# Buck-Boost_converter.net
KiCad netlist of a schematic drawn in Altium Designer
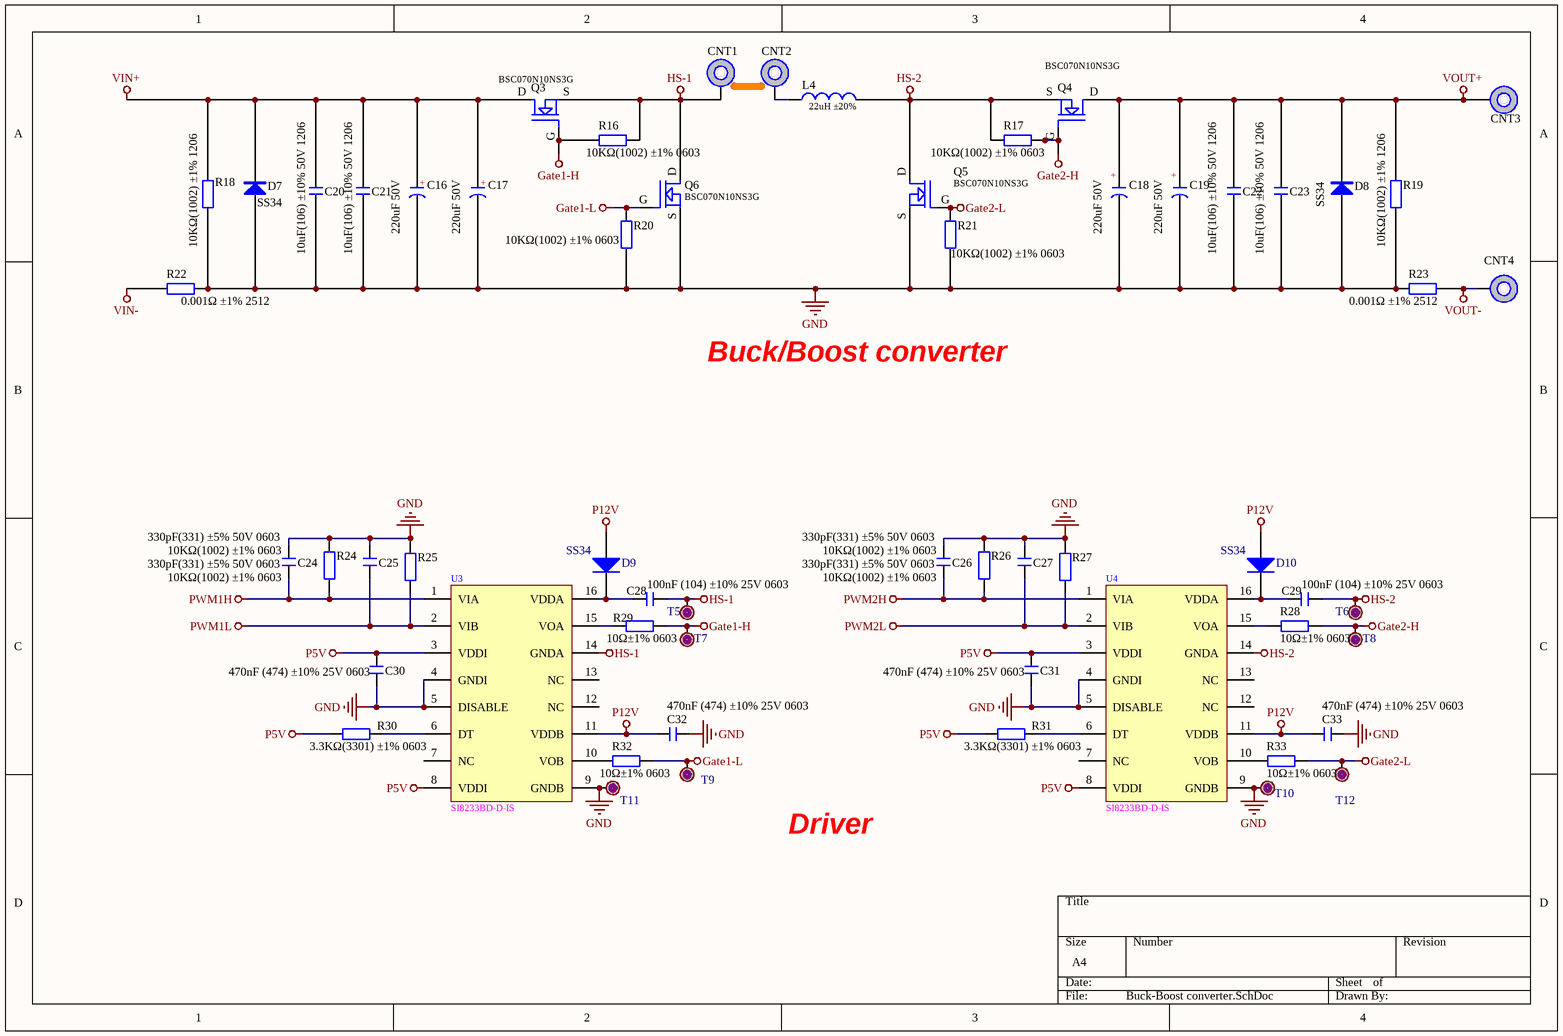
[diagram p0: Buck-Boost converter.SchDoc]

(export (version "E")
  (design (tool "Eeschema 10.0.6"))
  (components
    (comp (ref "C16")
      (value "220uF 50V")
      (footprint "CE F(10*10.2)")
      (description "直插电解电容")
      (libsource (lib "") (part "CE_1"))
    )
    (comp (ref "C17")
      (value "220uF 50V")
      (footprint "1.10-电容:CE F(10*10.2)")
      (description "直插电解电容")
      (libsource (lib "") (part "CE_1"))
    )
    (comp (ref "C18")
      (value "220uF 50V")
      (footprint "CE F(10*10.2)")
      (description "直插电解电容")
      (libsource (lib "0.1 - 电阻-电容-电感") (part "CE"))
    )
    (comp (ref "C19")
      (value "220uF 50V")
      (footprint "CE F(10*10.2)")
      (description "直插电解电容")
      (libsource (lib "0.1 - 电阻-电容-电感") (part "CE"))
    )
    (comp (ref "C20")
      (value "10uF(106) ±10% 50V 1206")
      (footprint "C 1206_M")
      (description "贴片电容")
      (libsource (lib "0.1 - 电阻-电容-电感") (part "C"))
    )
    (comp (ref "C21")
      (value "10uF(106) ±10% 50V 1206")
      (footprint "C 1206_M")
      (description "贴片电容")
      (libsource (lib "0.1 - 电阻-电容-电感") (part "C"))
    )
    (comp (ref "C22")
      (value "10uF(106) ±10% 50V 1206")
      (footprint "C 1206_M")
      (description "贴片电容")
      (libsource (lib "0.1 - 电阻-电容-电感") (part "C"))
    )
    (comp (ref "C23")
      (value "10uF(106) ±10% 50V 1206")
      (footprint "C 1206_M")
      (description "贴片电容")
      (libsource (lib "0.1 - 电阻-电容-电感") (part "C"))
    )
    (comp (ref "C24")
      (value "330pF(331) ±5% 50V 0603")
      (footprint "C 0603_L")
      (description "贴片电容")
      (libsource (lib "0.1 - 电阻-电容-电感") (part "C"))
    )
    (comp (ref "C25")
      (value "330pF(331) ±5% 50V 0603")
      (footprint "C 0603_L")
      (description "贴片电容")
      (libsource (lib "0.1 - 电阻-电容-电感") (part "C"))
    )
    (comp (ref "C26")
      (value "330pF(331) ±5% 50V 0603")
      (footprint "C 0603_L")
      (description "贴片电容")
      (libsource (lib "0.1 - 电阻-电容-电感") (part "C"))
    )
    (comp (ref "C27")
      (value "330pF(331) ±5% 50V 0603")
      (footprint "C 0603_L")
      (description "贴片电容")
      (libsource (lib "0.1 - 电阻-电容-电感") (part "C"))
    )
    (comp (ref "C28")
      (value "100nF (104) ±10% 25V 0603")
      (footprint "C 0603_L")
      (description "贴片电容")
      (libsource (lib "0.1 - 电阻-电容-电感") (part "C"))
    )
    (comp (ref "C29")
      (value "100nF (104) ±10% 25V 0603")
      (footprint "C 0603_L")
      (description "贴片电容")
      (libsource (lib "0.1 - 电阻-电容-电感") (part "C"))
    )
    (comp (ref "C30")
      (value "470nF (474) ±10% 25V 0603")
      (footprint "C 0603_L")
      (description "贴片电容")
      (libsource (lib "0.1 - 电阻-电容-电感") (part "C"))
    )
    (comp (ref "C31")
      (value "470nF (474) ±10% 25V 0603")
      (footprint "C 0603_L")
      (description "贴片电容")
      (libsource (lib "0.1 - 电阻-电容-电感") (part "C"))
    )
    (comp (ref "C32")
      (value "470nF (474) ±10% 25V 0603")
      (footprint "C 0603_L")
      (description "贴片电容")
      (libsource (lib "0.1 - 电阻-电容-电感") (part "C"))
    )
    (comp (ref "C33")
      (value "470nF (474) ±10% 25V 0603")
      (footprint "C 0603_L")
      (description "贴片电容")
      (libsource (lib "0.1 - 电阻-电容-电感") (part "C"))
    )
    (comp (ref "CNT1") (value "CST") (footprint "M3") (libsource (lib "Schlib2") (part "SO3040")))
    (comp (ref "CNT2") (value "CST") (footprint "M3") (libsource (lib "Schlib2") (part "SO3040")))
    (comp (ref "CNT3") (value "CST") (footprint "M3") (libsource (lib "Schlib2") (part "SO3040")))
    (comp (ref "CNT4") (value "CST") (footprint "M3") (libsource (lib "Schlib2") (part "SO3040")))
    (comp (ref "D7")
      (value "SS34")
      (footprint "SMA")
      (description "整流二极管")
      (libsource (lib "0.2 - 二极管-整流桥") (part "1N4007"))
    )
    (comp (ref "D8")
      (value "SS34")
      (footprint "SMA")
      (description "整流二极管")
      (libsource (lib "0.2 - 二极管-整流桥") (part "1N4007"))
    )
    (comp (ref "D9")
      (value "SS34")
      (footprint "SMA")
      (description "Default Diode")
      (libsource (lib "Miscellaneous Devices") (part "Diode"))
    )
    (comp (ref "D10")
      (value "SS34")
      (footprint "SMA")
      (description "Default Diode")
      (libsource (lib "Miscellaneous Devices") (part "Diode"))
    )
    (comp (ref "L4")
      (value "22uH ±20%")
      (footprint "L-SMD-0630")
      (description "Inductor")
      (libsource (lib "034110_D2DPOWER_V2") (part "Inductor"))
    )
    (comp (ref "Q3")
      (value "BSC070N10NS3G")
      (footprint "PG-TDSON-8_5x6MM")
      (libsource (lib "*") (part "MOSFET N"))
    )
    (comp (ref "Q4")
      (value "BSC070N10NS3G")
      (footprint "PG-TDSON-8_5x6MM")
      (libsource (lib "*") (part "MOSFET N"))
    )
    (comp (ref "Q5")
      (value "BSC070N10NS3G")
      (footprint "PG-TDSON-8_5x6MM")
      (libsource (lib "*") (part "MOSFET N"))
    )
    (comp (ref "Q6")
      (value "BSC070N10NS3G")
      (footprint "PG-TDSON-8_5x6MM")
      (libsource (lib "*") (part "MOSFET N"))
    )
    (comp (ref "R16")
      (value "10KΩ(1002) ±1% 0603")
      (footprint "R 0603_L")
      (description "贴片电阻")
      (fields (field (name "版权归属") "来自淘宝 ID：黄晶宝石"))
      (libsource (lib "0.1 - 电阻-电容-电感") (part "R"))
    )
    (comp (ref "R17")
      (value "10KΩ(1002) ±1% 0603")
      (footprint "R 0603_L")
      (description "贴片电阻")
      (fields (field (name "版权归属") "来自淘宝 ID：黄晶宝石"))
      (libsource (lib "0.1 - 电阻-电容-电感") (part "R"))
    )
    (comp (ref "R18")
      (value "10KΩ(1002) ±1% 1206")
      (footprint "R 1206_L")
      (description "贴片电阻")
      (fields (field (name "版权归属") "来自淘宝 ID：黄晶宝石"))
      (libsource (lib "0.1 - 电阻-电容-电感") (part "R"))
    )
    (comp (ref "R19")
      (value "10KΩ(1002) ±1% 1206")
      (footprint "R 1206_L")
      (description "贴片电阻")
      (fields (field (name "版权归属") "来自淘宝 ID：黄晶宝石"))
      (libsource (lib "0.1 - 电阻-电容-电感") (part "R"))
    )
    (comp (ref "R20")
      (value "10KΩ(1002) ±1% 0603")
      (footprint "R 0603_L")
      (description "贴片电阻")
      (fields (field (name "版权归属") "来自淘宝 ID：黄晶宝石"))
      (libsource (lib "0.1 - 电阻-电容-电感") (part "R"))
    )
    (comp (ref "R21")
      (value "10KΩ(1002) ±1% 0603")
      (footprint "R 0603_L")
      (description "贴片电阻")
      (fields (field (name "版权归属") "来自淘宝 ID：黄晶宝石"))
      (libsource (lib "0.1 - 电阻-电容-电感") (part "R"))
    )
    (comp (ref "R22")
      (value "0.001Ω ±1% 2512")
      (footprint "R2512")
      (description "贴片电阻")
      (fields (field (name "版权归属") "来自淘宝 ID：黄晶宝石"))
      (libsource (lib "0.1 - 电阻-电容-电感") (part "R"))
    )
    (comp (ref "R23")
      (value "0.001Ω ±1% 2512")
      (footprint "R2512")
      (description "贴片电阻")
      (fields (field (name "版权归属") "来自淘宝 ID：黄晶宝石"))
      (libsource (lib "0.1 - 电阻-电容-电感") (part "R"))
    )
    (comp (ref "R24")
      (value "10KΩ(1002) ±1% 0603")
      (footprint "R 0603_L")
      (description "贴片电阻")
      (fields (field (name "版权归属") "来自淘宝 ID：黄晶宝石"))
      (libsource (lib "0.1 - 电阻-电容-电感") (part "R"))
    )
    (comp (ref "R25")
      (value "10KΩ(1002) ±1% 0603")
      (footprint "R 0603_L")
      (description "贴片电阻")
      (fields (field (name "版权归属") "来自淘宝 ID：黄晶宝石"))
      (libsource (lib "0.1 - 电阻-电容-电感") (part "R"))
    )
    (comp (ref "R26")
      (value "10KΩ(1002) ±1% 0603")
      (footprint "R0805_L")
      (description "贴片电阻")
      (fields (field (name "版权归属") "来自淘宝 ID：黄晶宝石"))
      (libsource (lib "0.1 - 电阻-电容-电感") (part "R"))
    )
    (comp (ref "R27")
      (value "10KΩ(1002) ±1% 0603")
      (footprint "R 0603_L")
      (description "贴片电阻")
      (fields (field (name "版权归属") "来自淘宝 ID：黄晶宝石"))
      (libsource (lib "0.1 - 电阻-电容-电感") (part "R"))
    )
    (comp (ref "R28")
      (value "10Ω±1% 0603")
      (footprint "R 0603_L")
      (description "贴片电阻")
      (fields (field (name "版权归属") "来自淘宝 ID：黄晶宝石"))
      (libsource (lib "0.1 - 电阻-电容-电感") (part "R"))
    )
    (comp (ref "R29")
      (value "10Ω±1% 0603")
      (footprint "R 0603_L")
      (description "贴片电阻")
      (fields (field (name "版权归属") "来自淘宝 ID：黄晶宝石"))
      (libsource (lib "0.1 - 电阻-电容-电感") (part "R"))
    )
    (comp (ref "R30")
      (value "3.3KΩ(3301) ±1% 0603")
      (footprint "R 0603_L")
      (description "贴片电阻")
      (fields (field (name "版权归属") "来自淘宝 ID：黄晶宝石"))
      (libsource (lib "0.1 - 电阻-电容-电感") (part "R"))
    )
    (comp (ref "R31")
      (value "3.3KΩ(3301) ±1% 0603")
      (footprint "R 0603_L")
      (description "贴片电阻")
      (fields (field (name "版权归属") "来自淘宝 ID：黄晶宝石"))
      (libsource (lib "0.1 - 电阻-电容-电感") (part "R"))
    )
    (comp (ref "R32")
      (value "10Ω±1% 0603")
      (footprint "R 0603_L")
      (description "贴片电阻")
      (fields (field (name "版权归属") "来自淘宝 ID：黄晶宝石"))
      (libsource (lib "0.1 - 电阻-电容-电感") (part "R"))
    )
    (comp (ref "R33")
      (value "10Ω±1% 0603")
      (footprint "R 0603_L")
      (description "贴片电阻")
      (fields (field (name "版权归属") "来自淘宝 ID：黄晶宝石"))
      (libsource (lib "0.1 - 电阻-电容-电感") (part "R"))
    )
    (comp (ref "T5") (value "TestP") (footprint "TestP") (libsource (lib "CSS02404A") (part "TestP")))
    (comp (ref "T6") (value "TestP") (footprint "TestP") (libsource (lib "CSS02404A") (part "TestP")))
    (comp (ref "T7") (value "TestP") (footprint "TestP") (libsource (lib "CSS02404A") (part "TestP")))
    (comp (ref "T8") (value "TestP") (footprint "TestP") (libsource (lib "CSS02404A") (part "TestP")))
    (comp (ref "T9") (value "TestP") (footprint "TestP") (libsource (lib "CSS02404A") (part "TestP")))
    (comp (ref "T10") (value "TestP") (footprint "TestP") (libsource (lib "CSS02404A") (part "TestP")))
    (comp (ref "T11") (value "TestP") (footprint "TestP") (libsource (lib "CSS02404A") (part "TestP")))
    (comp (ref "T12") (value "TestP") (footprint "TestP") (libsource (lib "CSS02404A") (part "TestP")))
    (comp (ref "U3") (value "SI8233BD-D-IS") (footprint "SOJ16T") (libsource (lib "Si8234") (part "Si8233")))
    (comp (ref "U4") (value "SI8233BD-D-IS") (footprint "SOJ16T") (libsource (lib "Si8234") (part "Si8233")))
  )
  (nets
    (net (code "1") (name "GND") (class "Default")
      (node (ref "C16") (pin "2") (pinfunction "K_2") (pintype "passive"))
      (node (ref "C17") (pin "2") (pinfunction "K_2") (pintype "passive"))
      (node (ref "C18") (pin "2") (pinfunction "K_2") (pintype "passive"))
      (node (ref "C19") (pin "2") (pinfunction "K_2") (pintype "passive"))
      (node (ref "C20") (pin "1") (pinfunction "1_1") (pintype "passive"))
      (node (ref "C21") (pin "1") (pinfunction "1_1") (pintype "passive"))
      (node (ref "C22") (pin "1") (pinfunction "1_1") (pintype "passive"))
      (node (ref "C23") (pin "1") (pinfunction "1_1") (pintype "passive"))
      (node (ref "C24") (pin "2") (pinfunction "2_2") (pintype "passive"))
      (node (ref "C25") (pin "2") (pinfunction "2_2") (pintype "passive"))
      (node (ref "C26") (pin "2") (pinfunction "2_2") (pintype "passive"))
      (node (ref "C27") (pin "2") (pinfunction "2_2") (pintype "passive"))
      (node (ref "C30") (pin "2") (pinfunction "2_2") (pintype "passive"))
      (node (ref "C31") (pin "2") (pinfunction "2_2") (pintype "passive"))
      (node (ref "C32") (pin "1") (pinfunction "1_1") (pintype "passive"))
      (node (ref "C33") (pin "1") (pinfunction "1_1") (pintype "passive"))
      (node (ref "D7") (pin "1") (pinfunction "A_1") (pintype "passive"))
      (node (ref "D8") (pin "1") (pinfunction "A_1") (pintype "passive"))
      (node (ref "Q5") (pin "S") (pinfunction "SOURCE_S") (pintype "passive"))
      (node (ref "Q6") (pin "S") (pinfunction "SOURCE_S") (pintype "passive"))
      (node (ref "R18") (pin "1") (pinfunction "1_1") (pintype "passive"))
      (node (ref "R19") (pin "1") (pinfunction "1_1") (pintype "passive"))
      (node (ref "R20") (pin "1") (pinfunction "1_1") (pintype "passive"))
      (node (ref "R21") (pin "1") (pinfunction "1_1") (pintype "passive"))
      (node (ref "R22") (pin "1") (pinfunction "1_1") (pintype "passive"))
      (node (ref "R23") (pin "1") (pinfunction "1_1") (pintype "passive"))
      (node (ref "R24") (pin "2") (pinfunction "2_2") (pintype "passive"))
      (node (ref "R25") (pin "2") (pinfunction "2_2") (pintype "passive"))
      (node (ref "R26") (pin "2") (pinfunction "2_2") (pintype "passive"))
      (node (ref "R27") (pin "2") (pinfunction "2_2") (pintype "passive"))
      (node (ref "T10") (pin "0") (pinfunction "0_0") (pintype "passive"))
      (node (ref "T11") (pin "0") (pinfunction "0_0") (pintype "passive"))
      (node (ref "U3") (pin "4") (pinfunction "GNDI_4") (pintype "passive"))
      (node (ref "U3") (pin "5") (pinfunction "DISABLE_5") (pintype "passive"))
      (node (ref "U3") (pin "9") (pinfunction "GNDB_9") (pintype "passive"))
      (node (ref "U4") (pin "4") (pinfunction "GNDI_4") (pintype "passive"))
      (node (ref "U4") (pin "5") (pinfunction "DISABLE_5") (pintype "passive"))
      (node (ref "U4") (pin "9") (pinfunction "GNDB_9") (pintype "passive"))
    )
    (net (code "2") (name "Gate1-H") (class "Default")
      (node (ref "Q3") (pin "G") (pinfunction "GATE_G") (pintype "passive"))
      (node (ref "R16") (pin "1") (pinfunction "1_1") (pintype "passive"))
      (node (ref "R29") (pin "1") (pinfunction "1_1") (pintype "passive"))
      (node (ref "T7") (pin "0") (pinfunction "0_0") (pintype "passive"))
    )
    (net (code "3") (name "Gate1-L") (class "Default")
      (node (ref "Q6") (pin "G") (pinfunction "GATE_G") (pintype "passive"))
      (node (ref "R20") (pin "2") (pinfunction "2_2") (pintype "passive"))
      (node (ref "R32") (pin "1") (pinfunction "1_1") (pintype "passive"))
      (node (ref "T9") (pin "0") (pinfunction "0_0") (pintype "passive"))
    )
    (net (code "4") (name "Gate2-H") (class "Default")
      (node (ref "Q4") (pin "G") (pinfunction "GATE_G") (pintype "passive"))
      (node (ref "R17") (pin "1") (pinfunction "1_1") (pintype "passive"))
      (node (ref "R28") (pin "1") (pinfunction "1_1") (pintype "passive"))
      (node (ref "T8") (pin "0") (pinfunction "0_0") (pintype "passive"))
    )
    (net (code "5") (name "Gate2-L") (class "Default")
      (node (ref "Q5") (pin "G") (pinfunction "GATE_G") (pintype "passive"))
      (node (ref "R21") (pin "2") (pinfunction "2_2") (pintype "passive"))
      (node (ref "R33") (pin "1") (pinfunction "1_1") (pintype "passive"))
      (node (ref "T12") (pin "0") (pinfunction "0_0") (pintype "passive"))
    )
    (net (code "6") (name "HS-1") (class "Default")
      (node (ref "C28") (pin "2") (pinfunction "2_2") (pintype "passive"))
      (node (ref "CNT1") (pin "1") (pinfunction "1_1") (pintype "passive"))
      (node (ref "Q3") (pin "S") (pinfunction "SOURCE_S") (pintype "passive"))
      (node (ref "Q6") (pin "D") (pinfunction "DRAIN_D") (pintype "passive"))
      (node (ref "R16") (pin "2") (pinfunction "2_2") (pintype "passive"))
      (node (ref "T5") (pin "0") (pinfunction "0_0") (pintype "passive"))
      (node (ref "U3") (pin "14") (pinfunction "GNDA_14") (pintype "passive"))
    )
    (net (code "7") (name "HS-2") (class "Default")
      (node (ref "C29") (pin "2") (pinfunction "2_2") (pintype "passive"))
      (node (ref "L4") (pin "2") (pintype "passive"))
      (node (ref "Q4") (pin "S") (pinfunction "SOURCE_S") (pintype "passive"))
      (node (ref "Q5") (pin "D") (pinfunction "DRAIN_D") (pintype "passive"))
      (node (ref "R17") (pin "2") (pinfunction "2_2") (pintype "passive"))
      (node (ref "T6") (pin "0") (pinfunction "0_0") (pintype "passive"))
      (node (ref "U4") (pin "14") (pinfunction "GNDA_14") (pintype "passive"))
    )
    (net (code "8") (name "Net-(CNT2-Pad1)_1") (class "Default")
      (node (ref "CNT2") (pin "1") (pinfunction "1_1") (pintype "passive"))
      (node (ref "L4") (pin "1") (pintype "passive"))
    )
    (net (code "9") (name "Net-(D9-K)") (class "Default")
      (node (ref "C28") (pin "1") (pinfunction "1_1") (pintype "passive"))
      (node (ref "D9") (pin "2") (pinfunction "K_2") (pintype "passive"))
      (node (ref "U3") (pin "16") (pinfunction "VDDA_16") (pintype "passive"))
    )
    (net (code "10") (name "Net-(D10-K)") (class "Default")
      (node (ref "C29") (pin "1") (pinfunction "1_1") (pintype "passive"))
      (node (ref "D10") (pin "2") (pinfunction "K_2") (pintype "passive"))
      (node (ref "U4") (pin "16") (pinfunction "VDDA_16") (pintype "passive"))
    )
    (net (code "11") (name "Net-(U3-DT)") (class "Default")
      (node (ref "R30") (pin "1") (pinfunction "1_1") (pintype "passive"))
      (node (ref "U3") (pin "6") (pinfunction "DT_6") (pintype "passive"))
    )
    (net (code "12") (name "Net-(U3-VOA)") (class "Default")
      (node (ref "R29") (pin "2") (pinfunction "2_2") (pintype "passive"))
      (node (ref "U3") (pin "15") (pinfunction "VOA_15") (pintype "passive"))
    )
    (net (code "13") (name "Net-(U3-VOB)") (class "Default")
      (node (ref "R32") (pin "2") (pinfunction "2_2") (pintype "passive"))
      (node (ref "U3") (pin "10") (pinfunction "VOB_10") (pintype "passive"))
    )
    (net (code "14") (name "Net-(U4-DT)") (class "Default")
      (node (ref "R31") (pin "1") (pinfunction "1_1") (pintype "passive"))
      (node (ref "U4") (pin "6") (pinfunction "DT_6") (pintype "passive"))
    )
    (net (code "15") (name "Net-(U4-VOA)") (class "Default")
      (node (ref "R28") (pin "2") (pinfunction "2_2") (pintype "passive"))
      (node (ref "U4") (pin "15") (pinfunction "VOA_15") (pintype "passive"))
    )
    (net (code "16") (name "Net-(U4-VOB)") (class "Default")
      (node (ref "R33") (pin "2") (pinfunction "2_2") (pintype "passive"))
      (node (ref "U4") (pin "10") (pinfunction "VOB_10") (pintype "passive"))
    )
    (net (code "17") (name "P5V") (class "Default")
      (node (ref "C30") (pin "1") (pinfunction "1_1") (pintype "passive"))
      (node (ref "C31") (pin "1") (pinfunction "1_1") (pintype "passive"))
      (node (ref "R30") (pin "2") (pinfunction "2_2") (pintype "passive"))
      (node (ref "R31") (pin "2") (pinfunction "2_2") (pintype "passive"))
      (node (ref "U3") (pin "3") (pinfunction "VDDI_3") (pintype "passive"))
      (node (ref "U3") (pin "8") (pinfunction "VDDI_8") (pintype "passive"))
      (node (ref "U4") (pin "3") (pinfunction "VDDI_3") (pintype "passive"))
      (node (ref "U4") (pin "8") (pinfunction "VDDI_8") (pintype "passive"))
    )
    (net (code "18") (name "P12V") (class "Default")
      (node (ref "C32") (pin "2") (pinfunction "2_2") (pintype "passive"))
      (node (ref "C33") (pin "2") (pinfunction "2_2") (pintype "passive"))
      (node (ref "D10") (pin "1") (pinfunction "A_1") (pintype "passive"))
      (node (ref "D9") (pin "1") (pinfunction "A_1") (pintype "passive"))
      (node (ref "U3") (pin "11") (pinfunction "VDDB_11") (pintype "passive"))
      (node (ref "U4") (pin "11") (pinfunction "VDDB_11") (pintype "passive"))
    )
    (net (code "19") (name "PWM1H") (class "Default")
      (node (ref "C24") (pin "1") (pinfunction "1_1") (pintype "passive"))
      (node (ref "R24") (pin "1") (pinfunction "1_1") (pintype "passive"))
      (node (ref "U3") (pin "1") (pinfunction "VIA_1") (pintype "passive"))
    )
    (net (code "20") (name "PWM1L") (class "Default")
      (node (ref "C25") (pin "1") (pinfunction "1_1") (pintype "passive"))
      (node (ref "R25") (pin "1") (pinfunction "1_1") (pintype "passive"))
      (node (ref "U3") (pin "2") (pinfunction "VIB_2") (pintype "passive"))
    )
    (net (code "21") (name "PWM2H") (class "Default")
      (node (ref "C26") (pin "1") (pinfunction "1_1") (pintype "passive"))
      (node (ref "R26") (pin "1") (pinfunction "1_1") (pintype "passive"))
      (node (ref "U4") (pin "1") (pinfunction "VIA_1") (pintype "passive"))
    )
    (net (code "22") (name "PWM2L") (class "Default")
      (node (ref "C27") (pin "1") (pinfunction "1_1") (pintype "passive"))
      (node (ref "R27") (pin "1") (pinfunction "1_1") (pintype "passive"))
      (node (ref "U4") (pin "2") (pinfunction "VIB_2") (pintype "passive"))
    )
    (net (code "23") (name "VIN+") (class "Default")
      (node (ref "C16") (pin "1") (pinfunction "A_1") (pintype "passive"))
      (node (ref "C17") (pin "1") (pinfunction "A_1") (pintype "passive"))
      (node (ref "C20") (pin "2") (pinfunction "2_2") (pintype "passive"))
      (node (ref "C21") (pin "2") (pinfunction "2_2") (pintype "passive"))
      (node (ref "D7") (pin "2") (pinfunction "K_2") (pintype "passive"))
      (node (ref "Q3") (pin "D") (pinfunction "DRAIN_D") (pintype "passive"))
      (node (ref "R18") (pin "2") (pinfunction "2_2") (pintype "passive"))
    )
    (net (code "24") (name "VIN-") (class "Default")
      (node (ref "R22") (pin "2") (pinfunction "2_2") (pintype "passive"))
    )
    (net (code "25") (name "VOUT+") (class "Default")
      (node (ref "C18") (pin "1") (pinfunction "A_1") (pintype "passive"))
      (node (ref "C19") (pin "1") (pinfunction "A_1") (pintype "passive"))
      (node (ref "C22") (pin "2") (pinfunction "2_2") (pintype "passive"))
      (node (ref "C23") (pin "2") (pinfunction "2_2") (pintype "passive"))
      (node (ref "CNT3") (pin "1") (pinfunction "1_1") (pintype "passive"))
      (node (ref "D8") (pin "2") (pinfunction "K_2") (pintype "passive"))
      (node (ref "Q4") (pin "D") (pinfunction "DRAIN_D") (pintype "passive"))
      (node (ref "R19") (pin "2") (pinfunction "2_2") (pintype "passive"))
    )
    (net (code "26") (name "VOUT-") (class "Default")
      (node (ref "CNT4") (pin "1") (pinfunction "1_1") (pintype "passive"))
      (node (ref "R23") (pin "2") (pinfunction "2_2") (pintype "passive"))
    )
    (net (code "27") (name "unconnected-(CNT1-Pad1)") (class "Default")
      (node (ref "CNT1") (pin "1") (pinfunction "1_1") (pintype "passive"))
    )
    (net (code "28") (name "unconnected-(CNT1-Pad1)_1") (class "Default")
      (node (ref "CNT1") (pin "1") (pinfunction "1_1") (pintype "passive"))
    )
    (net (code "29") (name "unconnected-(CNT1-Pad1)_2") (class "Default")
      (node (ref "CNT1") (pin "1") (pinfunction "1_1") (pintype "passive"))
    )
    (net (code "30") (name "unconnected-(CNT2-Pad1)") (class "Default")
      (node (ref "CNT2") (pin "1") (pinfunction "1_1") (pintype "passive"))
    )
    (net (code "31") (name "unconnected-(CNT2-Pad1)_2") (class "Default")
      (node (ref "CNT2") (pin "1") (pinfunction "1_1") (pintype "passive"))
    )
    (net (code "32") (name "unconnected-(CNT2-Pad1)_3") (class "Default")
      (node (ref "CNT2") (pin "1") (pinfunction "1_1") (pintype "passive"))
    )
    (net (code "33") (name "unconnected-(CNT3-Pad1)") (class "Default")
      (node (ref "CNT3") (pin "1") (pinfunction "1_1") (pintype "passive"))
    )
    (net (code "34") (name "unconnected-(CNT3-Pad1)_1") (class "Default")
      (node (ref "CNT3") (pin "1") (pinfunction "1_1") (pintype "passive"))
    )
    (net (code "35") (name "unconnected-(CNT3-Pad1)_2") (class "Default")
      (node (ref "CNT3") (pin "1") (pinfunction "1_1") (pintype "passive"))
    )
    (net (code "36") (name "unconnected-(CNT4-Pad1)") (class "Default")
      (node (ref "CNT4") (pin "1") (pinfunction "1_1") (pintype "passive"))
    )
    (net (code "37") (name "unconnected-(CNT4-Pad1)_1") (class "Default")
      (node (ref "CNT4") (pin "1") (pinfunction "1_1") (pintype "passive"))
    )
    (net (code "38") (name "unconnected-(CNT4-Pad1)_2") (class "Default")
      (node (ref "CNT4") (pin "1") (pinfunction "1_1") (pintype "passive"))
    )
    (net (code "39") (name "unconnected-(U3-NC-Pad7)") (class "Default")
      (node (ref "U3") (pin "7") (pinfunction "NC_7") (pintype "passive"))
    )
    (net (code "40") (name "unconnected-(U3-NC-Pad12)") (class "Default")
      (node (ref "U3") (pin "12") (pinfunction "NC_12") (pintype "passive"))
    )
    (net (code "41") (name "unconnected-(U3-NC-Pad13)") (class "Default")
      (node (ref "U3") (pin "13") (pinfunction "NC_13") (pintype "passive"))
    )
    (net (code "42") (name "unconnected-(U4-NC-Pad7)") (class "Default")
      (node (ref "U4") (pin "7") (pinfunction "NC_7") (pintype "passive"))
    )
    (net (code "43") (name "unconnected-(U4-NC-Pad12)") (class "Default")
      (node (ref "U4") (pin "12") (pinfunction "NC_12") (pintype "passive"))
    )
    (net (code "44") (name "unconnected-(U4-NC-Pad13)") (class "Default")
      (node (ref "U4") (pin "13") (pinfunction "NC_13") (pintype "passive"))
    )
  )
)
